# PGTN021_teensy.net
KiCad netlist of a schematic drawn in EAGLE
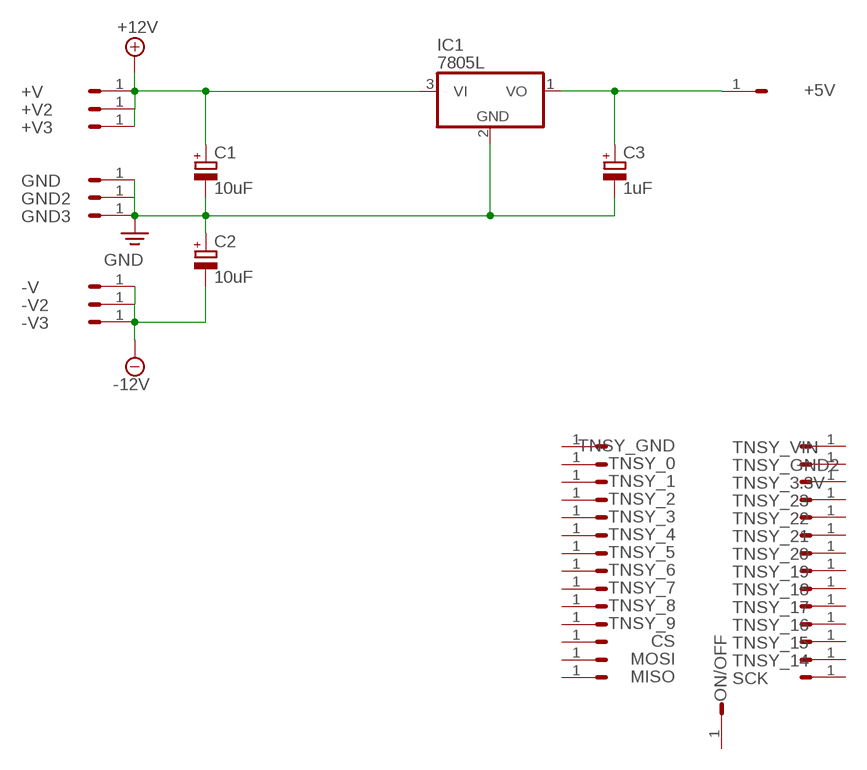
[diagram p0: schematic, sheet 1]

(export (version "E")
  (design (tool "Eeschema 10.0.6"))
  (components
    (comp (ref "+5V")
      (value "HEADER/MALE/01")
      (footprint "eagle-import:HEADER_MALE_01")
      (fields (field (name "SPICEPREFIX") "X"))
      (libsource (lib "eagle-import") (part "HEADER/MALE/01"))
    )
    (comp (ref "+V")
      (value "HEADER/MALE/01")
      (footprint "eagle-import:HEADER_MALE_01")
      (fields (field (name "SPICEPREFIX") "X"))
      (libsource (lib "eagle-import") (part "HEADER/MALE/01"))
    )
    (comp (ref "+V2")
      (value "HEADER/MALE/01")
      (footprint "eagle-import:HEADER_MALE_01")
      (fields (field (name "SPICEPREFIX") "X"))
      (libsource (lib "eagle-import") (part "HEADER/MALE/01"))
    )
    (comp (ref "+V3")
      (value "HEADER/MALE/01")
      (footprint "eagle-import:HEADER_MALE_01")
      (fields (field (name "SPICEPREFIX") "X"))
      (libsource (lib "eagle-import") (part "HEADER/MALE/01"))
    )
    (comp (ref "-V")
      (value "HEADER/MALE/01")
      (footprint "eagle-import:HEADER_MALE_01")
      (fields (field (name "SPICEPREFIX") "X"))
      (libsource (lib "eagle-import") (part "HEADER/MALE/01"))
    )
    (comp (ref "-V2")
      (value "HEADER/MALE/01")
      (footprint "eagle-import:HEADER_MALE_01")
      (fields (field (name "SPICEPREFIX") "X"))
      (libsource (lib "eagle-import") (part "HEADER/MALE/01"))
    )
    (comp (ref "-V3")
      (value "HEADER/MALE/01")
      (footprint "eagle-import:HEADER_MALE_01")
      (fields (field (name "SPICEPREFIX") "X"))
      (libsource (lib "eagle-import") (part "HEADER/MALE/01"))
    )
    (comp (ref "C1")
      (value "10uF")
      (footprint "eagle-import:E2,5-6")
      (fields (field (name "SPICEPREFIX") "C"))
      (libsource (lib "eagle-import") (part "CAPACITOR/POLARIZEDE2.5-6"))
    )
    (comp (ref "C2")
      (value "10uF")
      (footprint "eagle-import:E2,5-6")
      (fields (field (name "SPICEPREFIX") "C"))
      (libsource (lib "eagle-import") (part "CAPACITOR/POLARIZEDE2.5-6"))
    )
    (comp (ref "C3")
      (value "1uF")
      (footprint "eagle-import:E2,5-6")
      (fields (field (name "SPICEPREFIX") "C"))
      (libsource (lib "eagle-import") (part "CAPACITOR/POLARIZEDE2.5-6"))
    )
    (comp (ref "CS")
      (value "HEADER/MALE/01")
      (footprint "eagle-import:HEADER_MALE_01")
      (fields (field (name "SPICEPREFIX") "X"))
      (libsource (lib "eagle-import") (part "HEADER/MALE/01"))
    )
    (comp (ref "GND")
      (value "HEADER/MALE/01")
      (footprint "eagle-import:HEADER_MALE_01")
      (fields (field (name "SPICEPREFIX") "X"))
      (libsource (lib "eagle-import") (part "HEADER/MALE/01"))
    )
    (comp (ref "GND2")
      (value "HEADER/MALE/01")
      (footprint "eagle-import:HEADER_MALE_01")
      (fields (field (name "SPICEPREFIX") "X"))
      (libsource (lib "eagle-import") (part "HEADER/MALE/01"))
    )
    (comp (ref "GND3")
      (value "HEADER/MALE/01")
      (footprint "eagle-import:HEADER_MALE_01")
      (fields (field (name "SPICEPREFIX") "X"))
      (libsource (lib "eagle-import") (part "HEADER/MALE/01"))
    )
    (comp (ref "IC1")
      (value "7805L")
      (footprint "eagle-import:TO92")
      (libsource (lib "eagle-import") (part "78L05"))
    )
    (comp (ref "MISO")
      (value "HEADER/MALE/01")
      (footprint "eagle-import:HEADER_MALE_01")
      (fields (field (name "SPICEPREFIX") "X"))
      (libsource (lib "eagle-import") (part "HEADER/MALE/01"))
    )
    (comp (ref "MOSI")
      (value "HEADER/MALE/01")
      (footprint "eagle-import:HEADER_MALE_01")
      (fields (field (name "SPICEPREFIX") "X"))
      (libsource (lib "eagle-import") (part "HEADER/MALE/01"))
    )
    (comp (ref "ON/OFF")
      (value "HEADER/MALE/01")
      (footprint "eagle-import:HEADER_MALE_01")
      (fields (field (name "SPICEPREFIX") "X"))
      (libsource (lib "eagle-import") (part "HEADER/MALE/01"))
    )
    (comp (ref "SCK")
      (value "HEADER/MALE/01")
      (footprint "eagle-import:HEADER_MALE_01")
      (fields (field (name "SPICEPREFIX") "X"))
      (libsource (lib "eagle-import") (part "HEADER/MALE/01"))
    )
    (comp (ref "TNSY_0")
      (value "HEADER/MALE/01")
      (footprint "eagle-import:HEADER_MALE_01")
      (fields (field (name "SPICEPREFIX") "X"))
      (libsource (lib "eagle-import") (part "HEADER/MALE/01"))
    )
    (comp (ref "TNSY_1")
      (value "HEADER/MALE/01")
      (footprint "eagle-import:HEADER_MALE_01")
      (fields (field (name "SPICEPREFIX") "X"))
      (libsource (lib "eagle-import") (part "HEADER/MALE/01"))
    )
    (comp (ref "TNSY_2")
      (value "HEADER/MALE/01")
      (footprint "eagle-import:HEADER_MALE_01")
      (fields (field (name "SPICEPREFIX") "X"))
      (libsource (lib "eagle-import") (part "HEADER/MALE/01"))
    )
    (comp (ref "TNSY_3")
      (value "HEADER/MALE/01")
      (footprint "eagle-import:HEADER_MALE_01")
      (fields (field (name "SPICEPREFIX") "X"))
      (libsource (lib "eagle-import") (part "HEADER/MALE/01"))
    )
    (comp (ref "TNSY_3.3V")
      (value "HEADER/MALE/01")
      (footprint "eagle-import:HEADER_MALE_01")
      (fields (field (name "SPICEPREFIX") "X"))
      (libsource (lib "eagle-import") (part "HEADER/MALE/01"))
    )
    (comp (ref "TNSY_4")
      (value "HEADER/MALE/01")
      (footprint "eagle-import:HEADER_MALE_01")
      (fields (field (name "SPICEPREFIX") "X"))
      (libsource (lib "eagle-import") (part "HEADER/MALE/01"))
    )
    (comp (ref "TNSY_5")
      (value "HEADER/MALE/01")
      (footprint "eagle-import:HEADER_MALE_01")
      (fields (field (name "SPICEPREFIX") "X"))
      (libsource (lib "eagle-import") (part "HEADER/MALE/01"))
    )
    (comp (ref "TNSY_6")
      (value "HEADER/MALE/01")
      (footprint "eagle-import:HEADER_MALE_01")
      (fields (field (name "SPICEPREFIX") "X"))
      (libsource (lib "eagle-import") (part "HEADER/MALE/01"))
    )
    (comp (ref "TNSY_7")
      (value "HEADER/MALE/01")
      (footprint "eagle-import:HEADER_MALE_01")
      (fields (field (name "SPICEPREFIX") "X"))
      (libsource (lib "eagle-import") (part "HEADER/MALE/01"))
    )
    (comp (ref "TNSY_8")
      (value "HEADER/MALE/01")
      (footprint "eagle-import:HEADER_MALE_01")
      (fields (field (name "SPICEPREFIX") "X"))
      (libsource (lib "eagle-import") (part "HEADER/MALE/01"))
    )
    (comp (ref "TNSY_9")
      (value "HEADER/MALE/01")
      (footprint "eagle-import:HEADER_MALE_01")
      (fields (field (name "SPICEPREFIX") "X"))
      (libsource (lib "eagle-import") (part "HEADER/MALE/01"))
    )
    (comp (ref "TNSY_14")
      (value "HEADER/MALE/01")
      (footprint "eagle-import:HEADER_MALE_01")
      (fields (field (name "SPICEPREFIX") "X"))
      (libsource (lib "eagle-import") (part "HEADER/MALE/01"))
    )
    (comp (ref "TNSY_15")
      (value "HEADER/MALE/01")
      (footprint "eagle-import:HEADER_MALE_01")
      (fields (field (name "SPICEPREFIX") "X"))
      (libsource (lib "eagle-import") (part "HEADER/MALE/01"))
    )
    (comp (ref "TNSY_16")
      (value "HEADER/MALE/01")
      (footprint "eagle-import:HEADER_MALE_01")
      (fields (field (name "SPICEPREFIX") "X"))
      (libsource (lib "eagle-import") (part "HEADER/MALE/01"))
    )
    (comp (ref "TNSY_17")
      (value "HEADER/MALE/01")
      (footprint "eagle-import:HEADER_MALE_01")
      (fields (field (name "SPICEPREFIX") "X"))
      (libsource (lib "eagle-import") (part "HEADER/MALE/01"))
    )
    (comp (ref "TNSY_18")
      (value "HEADER/MALE/01")
      (footprint "eagle-import:HEADER_MALE_01")
      (fields (field (name "SPICEPREFIX") "X"))
      (libsource (lib "eagle-import") (part "HEADER/MALE/01"))
    )
    (comp (ref "TNSY_19")
      (value "HEADER/MALE/01")
      (footprint "eagle-import:HEADER_MALE_01")
      (fields (field (name "SPICEPREFIX") "X"))
      (libsource (lib "eagle-import") (part "HEADER/MALE/01"))
    )
    (comp (ref "TNSY_20")
      (value "HEADER/MALE/01")
      (footprint "eagle-import:HEADER_MALE_01")
      (fields (field (name "SPICEPREFIX") "X"))
      (libsource (lib "eagle-import") (part "HEADER/MALE/01"))
    )
    (comp (ref "TNSY_21")
      (value "HEADER/MALE/01")
      (footprint "eagle-import:HEADER_MALE_01")
      (fields (field (name "SPICEPREFIX") "X"))
      (libsource (lib "eagle-import") (part "HEADER/MALE/01"))
    )
    (comp (ref "TNSY_22")
      (value "HEADER/MALE/01")
      (footprint "eagle-import:HEADER_MALE_01")
      (fields (field (name "SPICEPREFIX") "X"))
      (libsource (lib "eagle-import") (part "HEADER/MALE/01"))
    )
    (comp (ref "TNSY_23")
      (value "HEADER/MALE/01")
      (footprint "eagle-import:HEADER_MALE_01")
      (fields (field (name "SPICEPREFIX") "X"))
      (libsource (lib "eagle-import") (part "HEADER/MALE/01"))
    )
    (comp (ref "TNSY_GND")
      (value "HEADER/MALE/01")
      (footprint "eagle-import:HEADER_MALE_01")
      (fields (field (name "SPICEPREFIX") "X"))
      (libsource (lib "eagle-import") (part "HEADER/MALE/01"))
    )
    (comp (ref "TNSY_GND2")
      (value "HEADER/MALE/01")
      (footprint "eagle-import:HEADER_MALE_01")
      (fields (field (name "SPICEPREFIX") "X"))
      (libsource (lib "eagle-import") (part "HEADER/MALE/01"))
    )
    (comp (ref "TNSY_VIN")
      (value "HEADER/MALE/01")
      (footprint "eagle-import:HEADER_MALE_01")
      (fields (field (name "SPICEPREFIX") "X"))
      (libsource (lib "eagle-import") (part "HEADER/MALE/01"))
    )
  )
  (nets
    (net (code "1") (name "+12V") (class "Default")
      (node (ref "+V") (pin "1") (pinfunction "3_1") (pintype "passive"))
      (node (ref "+V2") (pin "1") (pinfunction "3_1") (pintype "passive"))
      (node (ref "+V3") (pin "1") (pinfunction "3_1") (pintype "passive"))
      (node (ref "C1") (pin "+") (pinfunction "+_+") (pintype "passive"))
      (node (ref "IC1") (pin "3") (pinfunction "VI_3") (pintype "input"))
    )
    (net (code "2") (name "-12V") (class "Default")
      (node (ref "-V") (pin "1") (pinfunction "3_1") (pintype "passive"))
      (node (ref "-V2") (pin "1") (pinfunction "3_1") (pintype "passive"))
      (node (ref "-V3") (pin "1") (pinfunction "3_1") (pintype "passive"))
      (node (ref "C2") (pin "-") (pinfunction "-_-") (pintype "passive"))
    )
    (net (code "3") (name "GND") (class "Default")
      (node (ref "C1") (pin "-") (pinfunction "-_-") (pintype "passive"))
      (node (ref "C2") (pin "+") (pinfunction "+_+") (pintype "passive"))
      (node (ref "C3") (pin "-") (pinfunction "-_-") (pintype "passive"))
      (node (ref "GND") (pin "1") (pinfunction "3_1") (pintype "passive"))
      (node (ref "GND2") (pin "1") (pinfunction "3_1") (pintype "passive"))
      (node (ref "GND3") (pin "1") (pinfunction "3_1") (pintype "passive"))
      (node (ref "IC1") (pin "2") (pinfunction "GND_2") (pintype "passive"))
    )
    (net (code "4") (name "Net-(+5V-3)") (class "Default")
      (node (ref "+5V") (pin "1") (pinfunction "3_1") (pintype "passive"))
      (node (ref "C3") (pin "+") (pinfunction "+_+") (pintype "passive"))
      (node (ref "IC1") (pin "1") (pinfunction "VO_1") (pintype "passive"))
    )
    (net (code "5") (name "unconnected-(CS-3-Pad1)") (class "Default")
      (node (ref "CS") (pin "1") (pinfunction "3_1") (pintype "passive"))
    )
    (net (code "6") (name "unconnected-(MISO-3-Pad1)") (class "Default")
      (node (ref "MISO") (pin "1") (pinfunction "3_1") (pintype "passive"))
    )
    (net (code "7") (name "unconnected-(MOSI-3-Pad1)") (class "Default")
      (node (ref "MOSI") (pin "1") (pinfunction "3_1") (pintype "passive"))
    )
    (net (code "8") (name "unconnected-(ON/OFF-3-Pad1)") (class "Default")
      (node (ref "ON/OFF") (pin "1") (pinfunction "3_1") (pintype "passive"))
    )
    (net (code "9") (name "unconnected-(SCK-3-Pad1)") (class "Default")
      (node (ref "SCK") (pin "1") (pinfunction "3_1") (pintype "passive"))
    )
    (net (code "10") (name "unconnected-(TNSY_0-3-Pad1)") (class "Default")
      (node (ref "TNSY_0") (pin "1") (pinfunction "3_1") (pintype "passive"))
    )
    (net (code "11") (name "unconnected-(TNSY_1-3-Pad1)") (class "Default")
      (node (ref "TNSY_1") (pin "1") (pinfunction "3_1") (pintype "passive"))
    )
    (net (code "12") (name "unconnected-(TNSY_2-3-Pad1)") (class "Default")
      (node (ref "TNSY_2") (pin "1") (pinfunction "3_1") (pintype "passive"))
    )
    (net (code "13") (name "unconnected-(TNSY_3-3-Pad1)") (class "Default")
      (node (ref "TNSY_3") (pin "1") (pinfunction "3_1") (pintype "passive"))
    )
    (net (code "14") (name "unconnected-(TNSY_3.3V-3-Pad1)") (class "Default")
      (node (ref "TNSY_3.3V") (pin "1") (pinfunction "3_1") (pintype "passive"))
    )
    (net (code "15") (name "unconnected-(TNSY_4-3-Pad1)") (class "Default")
      (node (ref "TNSY_4") (pin "1") (pinfunction "3_1") (pintype "passive"))
    )
    (net (code "16") (name "unconnected-(TNSY_5-3-Pad1)") (class "Default")
      (node (ref "TNSY_5") (pin "1") (pinfunction "3_1") (pintype "passive"))
    )
    (net (code "17") (name "unconnected-(TNSY_6-3-Pad1)") (class "Default")
      (node (ref "TNSY_6") (pin "1") (pinfunction "3_1") (pintype "passive"))
    )
    (net (code "18") (name "unconnected-(TNSY_7-3-Pad1)") (class "Default")
      (node (ref "TNSY_7") (pin "1") (pinfunction "3_1") (pintype "passive"))
    )
    (net (code "19") (name "unconnected-(TNSY_8-3-Pad1)") (class "Default")
      (node (ref "TNSY_8") (pin "1") (pinfunction "3_1") (pintype "passive"))
    )
    (net (code "20") (name "unconnected-(TNSY_9-3-Pad1)") (class "Default")
      (node (ref "TNSY_9") (pin "1") (pinfunction "3_1") (pintype "passive"))
    )
    (net (code "21") (name "unconnected-(TNSY_14-3-Pad1)") (class "Default")
      (node (ref "TNSY_14") (pin "1") (pinfunction "3_1") (pintype "passive"))
    )
    (net (code "22") (name "unconnected-(TNSY_15-3-Pad1)") (class "Default")
      (node (ref "TNSY_15") (pin "1") (pinfunction "3_1") (pintype "passive"))
    )
    (net (code "23") (name "unconnected-(TNSY_16-3-Pad1)") (class "Default")
      (node (ref "TNSY_16") (pin "1") (pinfunction "3_1") (pintype "passive"))
    )
    (net (code "24") (name "unconnected-(TNSY_17-3-Pad1)") (class "Default")
      (node (ref "TNSY_17") (pin "1") (pinfunction "3_1") (pintype "passive"))
    )
    (net (code "25") (name "unconnected-(TNSY_18-3-Pad1)") (class "Default")
      (node (ref "TNSY_18") (pin "1") (pinfunction "3_1") (pintype "passive"))
    )
    (net (code "26") (name "unconnected-(TNSY_19-3-Pad1)") (class "Default")
      (node (ref "TNSY_19") (pin "1") (pinfunction "3_1") (pintype "passive"))
    )
    (net (code "27") (name "unconnected-(TNSY_20-3-Pad1)") (class "Default")
      (node (ref "TNSY_20") (pin "1") (pinfunction "3_1") (pintype "passive"))
    )
    (net (code "28") (name "unconnected-(TNSY_21-3-Pad1)") (class "Default")
      (node (ref "TNSY_21") (pin "1") (pinfunction "3_1") (pintype "passive"))
    )
    (net (code "29") (name "unconnected-(TNSY_22-3-Pad1)") (class "Default")
      (node (ref "TNSY_22") (pin "1") (pinfunction "3_1") (pintype "passive"))
    )
    (net (code "30") (name "unconnected-(TNSY_23-3-Pad1)") (class "Default")
      (node (ref "TNSY_23") (pin "1") (pinfunction "3_1") (pintype "passive"))
    )
    (net (code "31") (name "unconnected-(TNSY_GND-3-Pad1)") (class "Default")
      (node (ref "TNSY_GND") (pin "1") (pinfunction "3_1") (pintype "passive"))
    )
    (net (code "32") (name "unconnected-(TNSY_GND2-3-Pad1)") (class "Default")
      (node (ref "TNSY_GND2") (pin "1") (pinfunction "3_1") (pintype "passive"))
    )
    (net (code "33") (name "unconnected-(TNSY_VIN-3-Pad1)") (class "Default")
      (node (ref "TNSY_VIN") (pin "1") (pinfunction "3_1") (pintype "passive"))
    )
  )
)
